# torque.net
KiCad netlist of a schematic drawn in Altium Designer
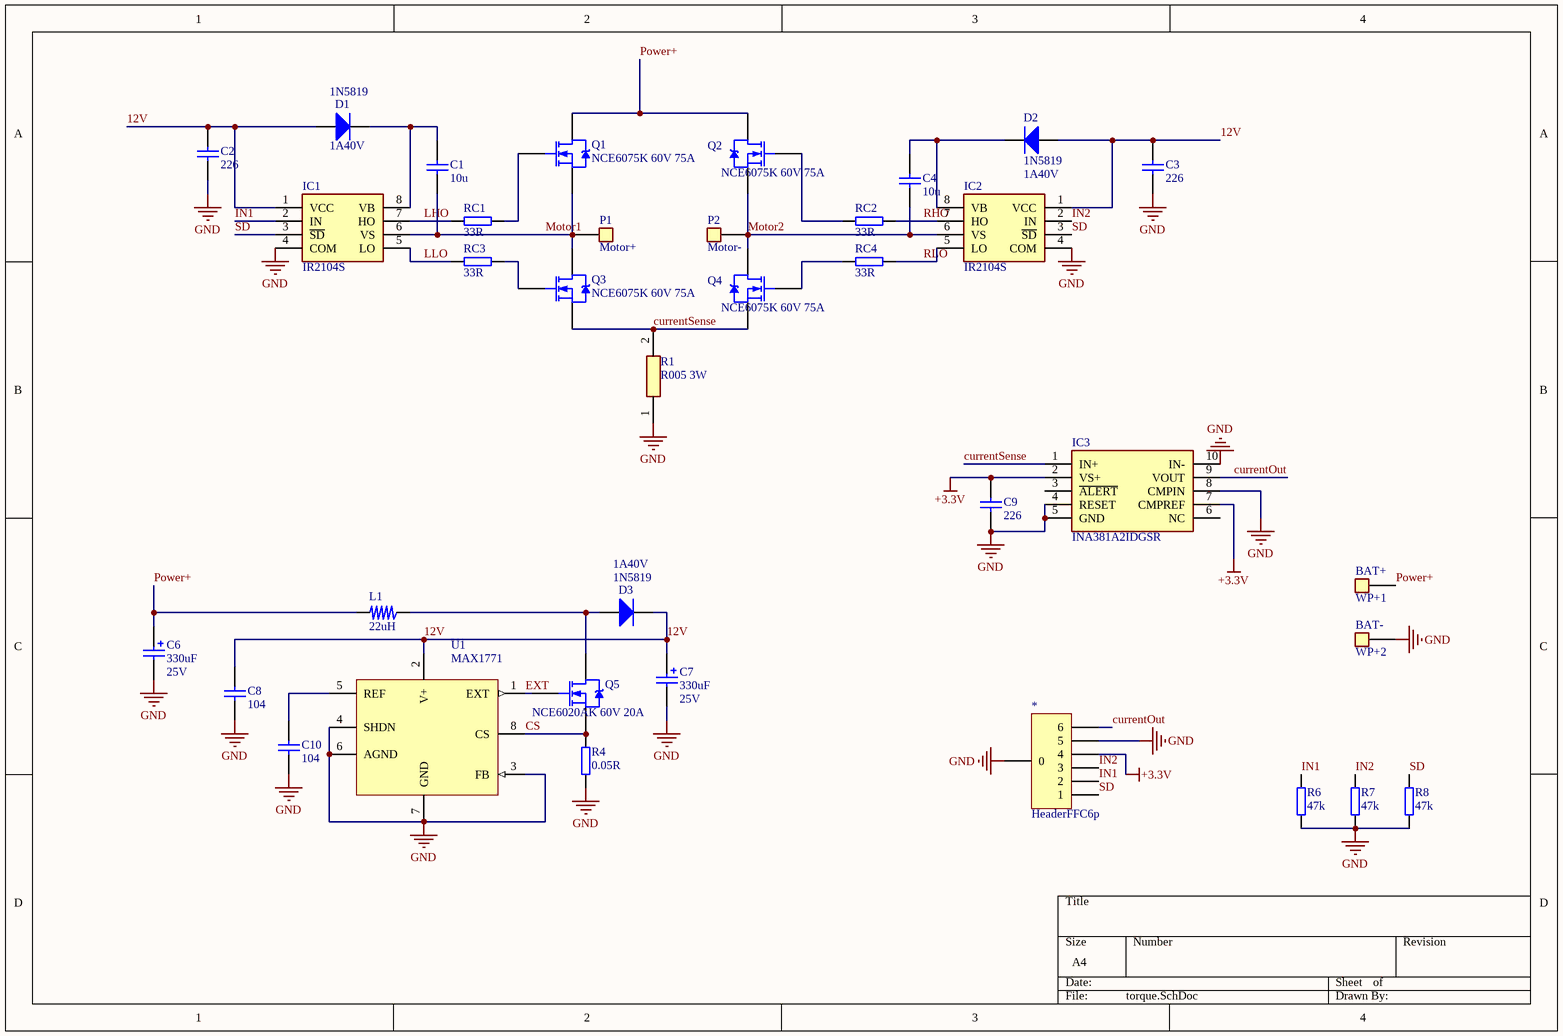
[diagram p0: torque.SchDoc]

(export (version "E")
  (design (tool "Eeschema 10.0.6"))
  (components
    (comp (ref "*")
      (value "HeaderFFC6p")
      (footprint "FH12-6S-1.0SH")
      (libsource (lib "BuildDev") (part "HeaderFFC6p"))
    )
    (comp (ref "C1")
      (value "10u")
      (footprint "CAPC3216[1206]")
      (description "Chip Capacitor, PSpice Model")
      (fields
        (field (name "TOLERANCE") "Y5V")
        (field (name "VOLTAGE") "3V")
        (field (name "PUBLISHER") "Altium Limited")
      )
      (libsource (lib "!)Miscellaneous Integrated Library") (part "Cap Chip 1"))
    )
    (comp (ref "C2")
      (value "226")
      (footprint "CAPC1608[0603]")
      (description "Chip Capacitor, PSpice Model")
      (fields
        (field (name "TOLERANCE") "Y5V")
        (field (name "VOLTAGE") "3V")
        (field (name "PUBLISHER") "Altium Limited")
      )
      (libsource (lib "!)Miscellaneous Integrated Library") (part "Cap Chip 1"))
    )
    (comp (ref "C3")
      (value "226")
      (footprint "CAPC1608[0603]")
      (description "Chip Capacitor, PSpice Model")
      (fields
        (field (name "TOLERANCE") "Y5V")
        (field (name "VOLTAGE") "3V")
        (field (name "PUBLISHER") "Altium Limited")
      )
      (libsource (lib "!)Miscellaneous Integrated Library") (part "Cap Chip 1"))
    )
    (comp (ref "C4")
      (value "10u")
      (footprint "CAPC3216[1206]")
      (description "Chip Capacitor, PSpice Model")
      (fields
        (field (name "TOLERANCE") "Y5V")
        (field (name "VOLTAGE") "3V")
        (field (name "PUBLISHER") "Altium Limited")
      )
      (libsource (lib "!)Miscellaneous Integrated Library") (part "Cap Chip 1"))
    )
    (comp (ref "C6")
      (value "330uF")
      (footprint "CAPS8")
      (description "Polarized Capacitor (Radial)")
      (fields (field (name "VOLTAGE") "25V") (field (name "PUBLISHER") "Altium Limited"))
      (libsource (lib "!)Miscellaneous Integrated Library") (part "Cap Solid"))
    )
    (comp (ref "C7")
      (value "330uF")
      (footprint "CAPS8")
      (description "Polarized Capacitor (Radial)")
      (fields (field (name "VOLTAGE") "25V") (field (name "PUBLISHER") "Altium Limited"))
      (libsource (lib "!)Miscellaneous Integrated Library") (part "Cap Solid"))
    )
    (comp (ref "C8")
      (value "104")
      (footprint "CAPC1608[0603]")
      (description "Chip Capacitor, PSpice Model")
      (fields
        (field (name "TOLERANCE") "Y5V")
        (field (name "VOLTAGE") "3V")
        (field (name "PUBLISHER") "Altium Limited")
      )
      (libsource (lib "!)Miscellaneous Integrated Library") (part "Cap Chip 1"))
    )
    (comp (ref "C9")
      (value "226")
      (footprint "CAPC1608[0603]")
      (description "Chip Capacitor, PSpice Model")
      (fields
        (field (name "TOLERANCE") "Y5V")
        (field (name "VOLTAGE") "3V")
        (field (name "PUBLISHER") "Altium Limited")
      )
      (libsource (lib "!)Miscellaneous Integrated Library") (part "Cap Chip 1"))
    )
    (comp (ref "C10")
      (value "104")
      (footprint "CAPC1608[0603]")
      (description "Chip Capacitor, PSpice Model")
      (fields
        (field (name "TOLERANCE") "Y5V")
        (field (name "VOLTAGE") "3V")
        (field (name "PUBLISHER") "Altium Limited")
      )
      (libsource (lib "!)Miscellaneous Integrated Library") (part "Cap Chip 1"))
    )
    (comp (ref "D1")
      (value "1N5819")
      (footprint "SOD-323")
      (description "MELF Diode")
      (fields
        (field (name "PARTNUMBER") "1N5819")
        (field (name "VOLTAGE") "1A40V")
        (field (name "PUBLISHER") "Altium Limited")
      )
      (libsource (lib "!)Miscellaneous Integrated Library") (part "Diode SOD"))
    )
    (comp (ref "D2")
      (value "1N5819")
      (footprint "SOD-323")
      (description "MELF Diode")
      (fields
        (field (name "PARTNUMBER") "1N5819")
        (field (name "VOLTAGE") "1A40V")
        (field (name "PUBLISHER") "Altium Limited")
      )
      (libsource (lib "!)Miscellaneous Integrated Library") (part "Diode SOD"))
    )
    (comp (ref "D3")
      (value "1N5819")
      (footprint "SOD-323")
      (description "MELF Diode")
      (fields
        (field (name "PARTNUMBER") "1N5819")
        (field (name "VOLTAGE") "1A40V")
        (field (name "PUBLISHER") "Altium Limited")
      )
      (libsource (lib "!)Miscellaneous Integrated Library") (part "Diode SOD"))
    )
    (comp (ref "IC1")
      (value "IR2104S")
      (footprint "SOIC127P600X175-8N")
      (description "Integrated Circuit")
      (libsource (lib "SamacSys") (part "IR2104S"))
    )
    (comp (ref "IC2")
      (value "IR2104S")
      (footprint "SOIC127P600X175-8N")
      (description "Integrated Circuit")
      (libsource (lib "") (part "IR2104S_1"))
    )
    (comp (ref "IC3")
      (value "INA381A2IDGSR")
      (footprint "SOP50P490X110-10N")
      (description "Integrated Circuit")
      (fields
        (field (name "MANUFACTURER_PART_NUMBER") "INA381A1IDGSR")
        (field (name "MOUSER PART NUMBER") "595-INA381A1IDGSR")
      )
      (libsource (lib "SamacSys") (part "INA381A1IDGSR"))
    )
    (comp (ref "L1") (value "22uH") (footprint "WHC0630") (libsource (lib "BuildDev") (part "L")))
    (comp (ref "P1")
      (value "Motor+")
      (footprint "WirePadSingleSide")
      (description "Wire soldering pad.")
      (libsource (lib "") (part "Wire Pad_1"))
    )
    (comp (ref "P2")
      (value "Motor-")
      (footprint "WirePadSingleSide")
      (description "Wire soldering pad.")
      (libsource (lib "!)Miscellaneous Integrated Library") (part "Wire Pad"))
    )
    (comp (ref "Q1")
      (value "NCE6075K 60V 75A")
      (footprint "TO-252")
      (libsource (lib "BuildDev") (part "NMOS"))
    )
    (comp (ref "Q2")
      (value "NCE6075K 60V 75A")
      (footprint "TO-252")
      (libsource (lib "BuildDev") (part "NMOS"))
    )
    (comp (ref "Q3")
      (value "NCE6075K 60V 75A")
      (footprint "TO-252")
      (libsource (lib "BuildDev") (part "NMOS"))
    )
    (comp (ref "Q4")
      (value "NCE6075K 60V 75A")
      (footprint "TO-252")
      (libsource (lib "BuildDev") (part "NMOS"))
    )
    (comp (ref "Q5")
      (value "NCE6020AK 60V 20A")
      (footprint "TO-252")
      (libsource (lib "BuildDev") (part "NMOS"))
    )
    (comp (ref "R1")
      (value "R005 3W")
      (footprint "R2512")
      (description "Resistor")
      (fields
        (field (name "MANUFACTURER_PART_NUMBER") "CR2512-F/-1R00ELF")
        (field (name "MOUSER PART NUMBER") "652-CR2512-F/1R00ELF")
      )
      (libsource (lib "SamacSys") (part "CR2512"))
    )
    (comp (ref "R4")
      (value "0.05R")
      (footprint "RESC3225[1210]")
      (description "Chip Resistor, PSpice Model, IPC PCB Library Drawing")
      (fields
        (field (name "TOLERANCE") "5%")
        (field (name "Comment") "0.05")
        (field (name "PUBLISHER") "Altium Limited")
      )
      (libsource (lib "!)Miscellaneous Integrated Library") (part "Res Chip 2p 1"))
    )
    (comp (ref "R6")
      (value "47k")
      (footprint "RESC1608[0603]")
      (description "Chip Resistor, PSpice Model, IPC PCB Library Drawing")
      (fields (field (name "TOLERANCE") "5%") (field (name "PUBLISHER") "Altium Limited"))
      (libsource (lib "!)Miscellaneous Integrated Library") (part "Res Chip 2p 1"))
    )
    (comp (ref "R7")
      (value "47k")
      (footprint "RESC1608[0603]")
      (description "Chip Resistor, PSpice Model, IPC PCB Library Drawing")
      (fields (field (name "TOLERANCE") "5%") (field (name "PUBLISHER") "Altium Limited"))
      (libsource (lib "!)Miscellaneous Integrated Library") (part "Res Chip 2p 1"))
    )
    (comp (ref "R8")
      (value "47k")
      (footprint "RESC1608[0603]")
      (description "Chip Resistor, PSpice Model, IPC PCB Library Drawing")
      (fields (field (name "TOLERANCE") "5%") (field (name "PUBLISHER") "Altium Limited"))
      (libsource (lib "!)Miscellaneous Integrated Library") (part "Res Chip 2p 1"))
    )
    (comp (ref "RC1")
      (value "33R")
      (footprint "RESC1608[0603]")
      (description "Chip Resistor, PSpice Model, IPC PCB Library Drawing")
      (fields (field (name "TOLERANCE") "5%") (field (name "PUBLISHER") "Altium Limited"))
      (libsource (lib "!)Miscellaneous Integrated Library") (part "Res Chip 2p 1"))
    )
    (comp (ref "RC2")
      (value "33R")
      (footprint "RESC1608[0603]")
      (description "Chip Resistor, PSpice Model, IPC PCB Library Drawing")
      (fields (field (name "TOLERANCE") "5%") (field (name "PUBLISHER") "Altium Limited"))
      (libsource (lib "!)Miscellaneous Integrated Library") (part "Res Chip 2p 1"))
    )
    (comp (ref "RC3")
      (value "33R")
      (footprint "RESC1608[0603]")
      (description "Chip Resistor, PSpice Model, IPC PCB Library Drawing")
      (fields (field (name "TOLERANCE") "5%") (field (name "PUBLISHER") "Altium Limited"))
      (libsource (lib "!)Miscellaneous Integrated Library") (part "Res Chip 2p 1"))
    )
    (comp (ref "RC4")
      (value "33R")
      (footprint "RESC1608[0603]")
      (description "Chip Resistor, PSpice Model, IPC PCB Library Drawing")
      (fields (field (name "TOLERANCE") "5%") (field (name "PUBLISHER") "Altium Limited"))
      (libsource (lib "!)Miscellaneous Integrated Library") (part "Res Chip 2p 1"))
    )
    (comp (ref "U1")
      (value "MAX1771")
      (footprint "SOIC8")
      (description "DC-to-DC Converter Control Circuit")
      (fields (field (name "PARTNUMBER") "MAX1771"))
      (libsource (lib "!)Miscellaneous Integrated Library") (part "MAX1771"))
    )
    (comp (ref "WP+1")
      (value "BAT+")
      (footprint "WirePadSingleSide")
      (description "Wire soldering pad.")
      (libsource (lib "!)Miscellaneous Integrated Library") (part "Wire Pad"))
    )
    (comp (ref "WP+2")
      (value "BAT-")
      (footprint "WirePadSingleSide")
      (description "Wire soldering pad.")
      (libsource (lib "!)Miscellaneous Integrated Library") (part "Wire Pad"))
    )
  )
  (nets
    (net (code "1") (name "+3.3V") (class "Default")
      (node (ref "*") (pin "4") (pinfunction "4_4") (pintype "passive"))
      (node (ref "C9") (pin "1") (pinfunction "1_1") (pintype "passive"))
      (node (ref "IC3") (pin "2") (pinfunction "VS+_2") (pintype "passive"))
      (node (ref "IC3") (pin "7") (pinfunction "CMPREF_7") (pintype "passive"))
    )
    (net (code "2") (name "/12V") (class "Default")
      (node (ref "C2") (pin "1") (pinfunction "1_1") (pintype "passive"))
      (node (ref "C3") (pin "1") (pinfunction "1_1") (pintype "passive"))
      (node (ref "C7") (pin "1") (pinfunction "1_1") (pintype "passive"))
      (node (ref "C8") (pin "1") (pinfunction "1_1") (pintype "passive"))
      (node (ref "D1") (pin "A") (pinfunction "A_A") (pintype "passive"))
      (node (ref "D2") (pin "A") (pinfunction "A_A") (pintype "passive"))
      (node (ref "D3") (pin "K") (pinfunction "K_K") (pintype "passive"))
      (node (ref "IC1") (pin "1") (pinfunction "VCC_1") (pintype "passive"))
      (node (ref "IC2") (pin "1") (pinfunction "VCC_1") (pintype "passive"))
      (node (ref "U1") (pin "2") (pinfunction "V+_2") (pintype "power_in"))
    )
    (net (code "3") (name "/CS") (class "Default")
      (node (ref "Q5") (pin "3") (pinfunction "S_3") (pintype "passive"))
      (node (ref "R4") (pin "1") (pinfunction "1_1") (pintype "passive"))
      (node (ref "U1") (pin "8") (pinfunction "CS_8") (pintype "passive"))
    )
    (net (code "4") (name "/EXT") (class "Default")
      (node (ref "Q5") (pin "1") (pinfunction "G_1") (pintype "passive"))
      (node (ref "U1") (pin "1") (pinfunction "EXT_1") (pintype "output"))
    )
    (net (code "5") (name "/IN1") (class "Default")
      (node (ref "*") (pin "2") (pinfunction "2_2") (pintype "passive"))
      (node (ref "IC1") (pin "2") (pinfunction "IN_2") (pintype "passive"))
      (node (ref "R6") (pin "2") (pinfunction "2_2") (pintype "passive"))
    )
    (net (code "6") (name "/IN2") (class "Default")
      (node (ref "*") (pin "3") (pinfunction "3_3") (pintype "passive"))
      (node (ref "IC2") (pin "2") (pinfunction "IN_2") (pintype "passive"))
      (node (ref "R7") (pin "2") (pinfunction "2_2") (pintype "passive"))
    )
    (net (code "7") (name "/LHO") (class "Default")
      (node (ref "IC1") (pin "7") (pinfunction "HO_7") (pintype "passive"))
      (node (ref "RC1") (pin "1") (pinfunction "1_1") (pintype "passive"))
    )
    (net (code "8") (name "/LLO") (class "Default")
      (node (ref "IC1") (pin "5") (pinfunction "LO_5") (pintype "passive"))
      (node (ref "RC3") (pin "1") (pinfunction "1_1") (pintype "passive"))
    )
    (net (code "9") (name "/Motor1") (class "Default")
      (node (ref "C1") (pin "2") (pinfunction "2_2") (pintype "passive"))
      (node (ref "IC1") (pin "6") (pinfunction "VS_6") (pintype "passive"))
      (node (ref "P1") (pin "1") (pinfunction "0_1") (pintype "passive"))
      (node (ref "Q1") (pin "3") (pinfunction "S_3") (pintype "passive"))
      (node (ref "Q3") (pin "2") (pinfunction "D_2") (pintype "passive"))
    )
    (net (code "10") (name "/Motor2") (class "Default")
      (node (ref "C4") (pin "2") (pinfunction "2_2") (pintype "passive"))
      (node (ref "IC2") (pin "6") (pinfunction "VS_6") (pintype "passive"))
      (node (ref "P2") (pin "1") (pinfunction "0_1") (pintype "passive"))
      (node (ref "Q2") (pin "3") (pinfunction "S_3") (pintype "passive"))
      (node (ref "Q4") (pin "2") (pinfunction "D_2") (pintype "passive"))
    )
    (net (code "11") (name "/Power+") (class "Default")
      (node (ref "C6") (pin "1") (pinfunction "1_1") (pintype "passive"))
      (node (ref "L1") (pin "2") (pinfunction "2_2") (pintype "passive"))
      (node (ref "Q1") (pin "2") (pinfunction "D_2") (pintype "passive"))
      (node (ref "Q2") (pin "2") (pinfunction "D_2") (pintype "passive"))
      (node (ref "WP+1") (pin "1") (pinfunction "0_1") (pintype "passive"))
    )
    (net (code "12") (name "/RHO") (class "Default")
      (node (ref "IC2") (pin "7") (pinfunction "HO_7") (pintype "passive"))
      (node (ref "RC2") (pin "1") (pinfunction "1_1") (pintype "passive"))
    )
    (net (code "13") (name "/RLO") (class "Default")
      (node (ref "IC2") (pin "5") (pinfunction "LO_5") (pintype "passive"))
      (node (ref "RC4") (pin "1") (pinfunction "1_1") (pintype "passive"))
    )
    (net (code "14") (name "/SD") (class "Default")
      (node (ref "*") (pin "1") (pinfunction "1_1") (pintype "passive"))
      (node (ref "IC1") (pin "3") (pinfunction "~{SD}_3") (pintype "passive"))
      (node (ref "IC2") (pin "3") (pinfunction "~{SD}_3") (pintype "passive"))
      (node (ref "R8") (pin "2") (pinfunction "2_2") (pintype "passive"))
    )
    (net (code "15") (name "/currentOut") (class "Default")
      (node (ref "*") (pin "6") (pinfunction "6_6") (pintype "passive"))
      (node (ref "IC3") (pin "9") (pinfunction "VOUT_9") (pintype "passive"))
    )
    (net (code "16") (name "/currentSense") (class "Default")
      (node (ref "IC3") (pin "1") (pinfunction "IN+_1") (pintype "passive"))
      (node (ref "Q3") (pin "3") (pinfunction "S_3") (pintype "passive"))
      (node (ref "Q4") (pin "3") (pinfunction "S_3") (pintype "passive"))
      (node (ref "R1") (pin "2") (pinfunction "2_2") (pintype "passive"))
    )
    (net (code "17") (name "GND") (class "Default")
      (node (ref "*") (pin "0") (pinfunction "0_0") (pintype "passive"))
      (node (ref "*") (pin "5") (pinfunction "5_5") (pintype "passive"))
      (node (ref "C10") (pin "1") (pinfunction "1_1") (pintype "passive"))
      (node (ref "C2") (pin "2") (pinfunction "2_2") (pintype "passive"))
      (node (ref "C3") (pin "2") (pinfunction "2_2") (pintype "passive"))
      (node (ref "C6") (pin "2") (pinfunction "2_2") (pintype "passive"))
      (node (ref "C7") (pin "2") (pinfunction "2_2") (pintype "passive"))
      (node (ref "C8") (pin "2") (pinfunction "2_2") (pintype "passive"))
      (node (ref "C9") (pin "2") (pinfunction "2_2") (pintype "passive"))
      (node (ref "IC1") (pin "4") (pinfunction "COM_4") (pintype "passive"))
      (node (ref "IC2") (pin "4") (pinfunction "COM_4") (pintype "passive"))
      (node (ref "IC3") (pin "10") (pinfunction "IN-_10") (pintype "passive"))
      (node (ref "IC3") (pin "4") (pinfunction "RESET_4") (pintype "passive"))
      (node (ref "IC3") (pin "5") (pinfunction "GND_5") (pintype "passive"))
      (node (ref "IC3") (pin "8") (pinfunction "CMPIN_8") (pintype "passive"))
      (node (ref "R1") (pin "1") (pinfunction "1_1") (pintype "passive"))
      (node (ref "R4") (pin "2") (pinfunction "2_2") (pintype "passive"))
      (node (ref "R6") (pin "1") (pinfunction "1_1") (pintype "passive"))
      (node (ref "R7") (pin "1") (pinfunction "1_1") (pintype "passive"))
      (node (ref "R8") (pin "1") (pinfunction "1_1") (pintype "passive"))
      (node (ref "U1") (pin "3") (pinfunction "FB_3") (pintype "input"))
      (node (ref "U1") (pin "4") (pinfunction "SHDN_4") (pintype "power_in"))
      (node (ref "U1") (pin "6") (pinfunction "AGND_6") (pintype "power_in"))
      (node (ref "U1") (pin "7") (pinfunction "GND_7") (pintype "power_in"))
      (node (ref "WP+2") (pin "1") (pinfunction "0_1") (pintype "passive"))
    )
    (net (code "18") (name "Net-(IC1-VB)") (class "Default")
      (node (ref "C1") (pin "1") (pinfunction "1_1") (pintype "passive"))
      (node (ref "D1") (pin "K") (pinfunction "K_K") (pintype "passive"))
      (node (ref "IC1") (pin "8") (pinfunction "VB_8") (pintype "passive"))
    )
    (net (code "19") (name "Net-(IC2-VB)") (class "Default")
      (node (ref "C4") (pin "1") (pinfunction "1_1") (pintype "passive"))
      (node (ref "D2") (pin "K") (pinfunction "K_K") (pintype "passive"))
      (node (ref "IC2") (pin "8") (pinfunction "VB_8") (pintype "passive"))
    )
    (net (code "20") (name "Net-(Q1-G)") (class "Default")
      (node (ref "Q1") (pin "1") (pinfunction "G_1") (pintype "passive"))
      (node (ref "RC1") (pin "2") (pinfunction "2_2") (pintype "passive"))
    )
    (net (code "21") (name "Net-(Q2-G)") (class "Default")
      (node (ref "Q2") (pin "1") (pinfunction "G_1") (pintype "passive"))
      (node (ref "RC2") (pin "2") (pinfunction "2_2") (pintype "passive"))
    )
    (net (code "22") (name "Net-(Q3-G)") (class "Default")
      (node (ref "Q3") (pin "1") (pinfunction "G_1") (pintype "passive"))
      (node (ref "RC3") (pin "2") (pinfunction "2_2") (pintype "passive"))
    )
    (net (code "23") (name "Net-(Q4-G)") (class "Default")
      (node (ref "Q4") (pin "1") (pinfunction "G_1") (pintype "passive"))
      (node (ref "RC4") (pin "2") (pinfunction "2_2") (pintype "passive"))
    )
    (net (code "24") (name "Net-(Q5-D)") (class "Default")
      (node (ref "D3") (pin "A") (pinfunction "A_A") (pintype "passive"))
      (node (ref "L1") (pin "1") (pinfunction "1_1") (pintype "passive"))
      (node (ref "Q5") (pin "2") (pinfunction "D_2") (pintype "passive"))
    )
    (net (code "25") (name "Net-(U1-REF)") (class "Default")
      (node (ref "C10") (pin "2") (pinfunction "2_2") (pintype "passive"))
      (node (ref "U1") (pin "5") (pinfunction "REF_5") (pintype "passive"))
    )
    (net (code "26") (name "unconnected-(IC3-NC-Pad6)") (class "Default")
      (node (ref "IC3") (pin "6") (pinfunction "NC_6") (pintype "passive"))
    )
    (net (code "27") (name "unconnected-(IC3-~{ALERT}-Pad3)") (class "Default")
      (node (ref "IC3") (pin "3") (pinfunction "~{ALERT}_3") (pintype "passive"))
    )
  )
)
